# 06_MCU.net
KiCad netlist of a schematic drawn in Altium Designer
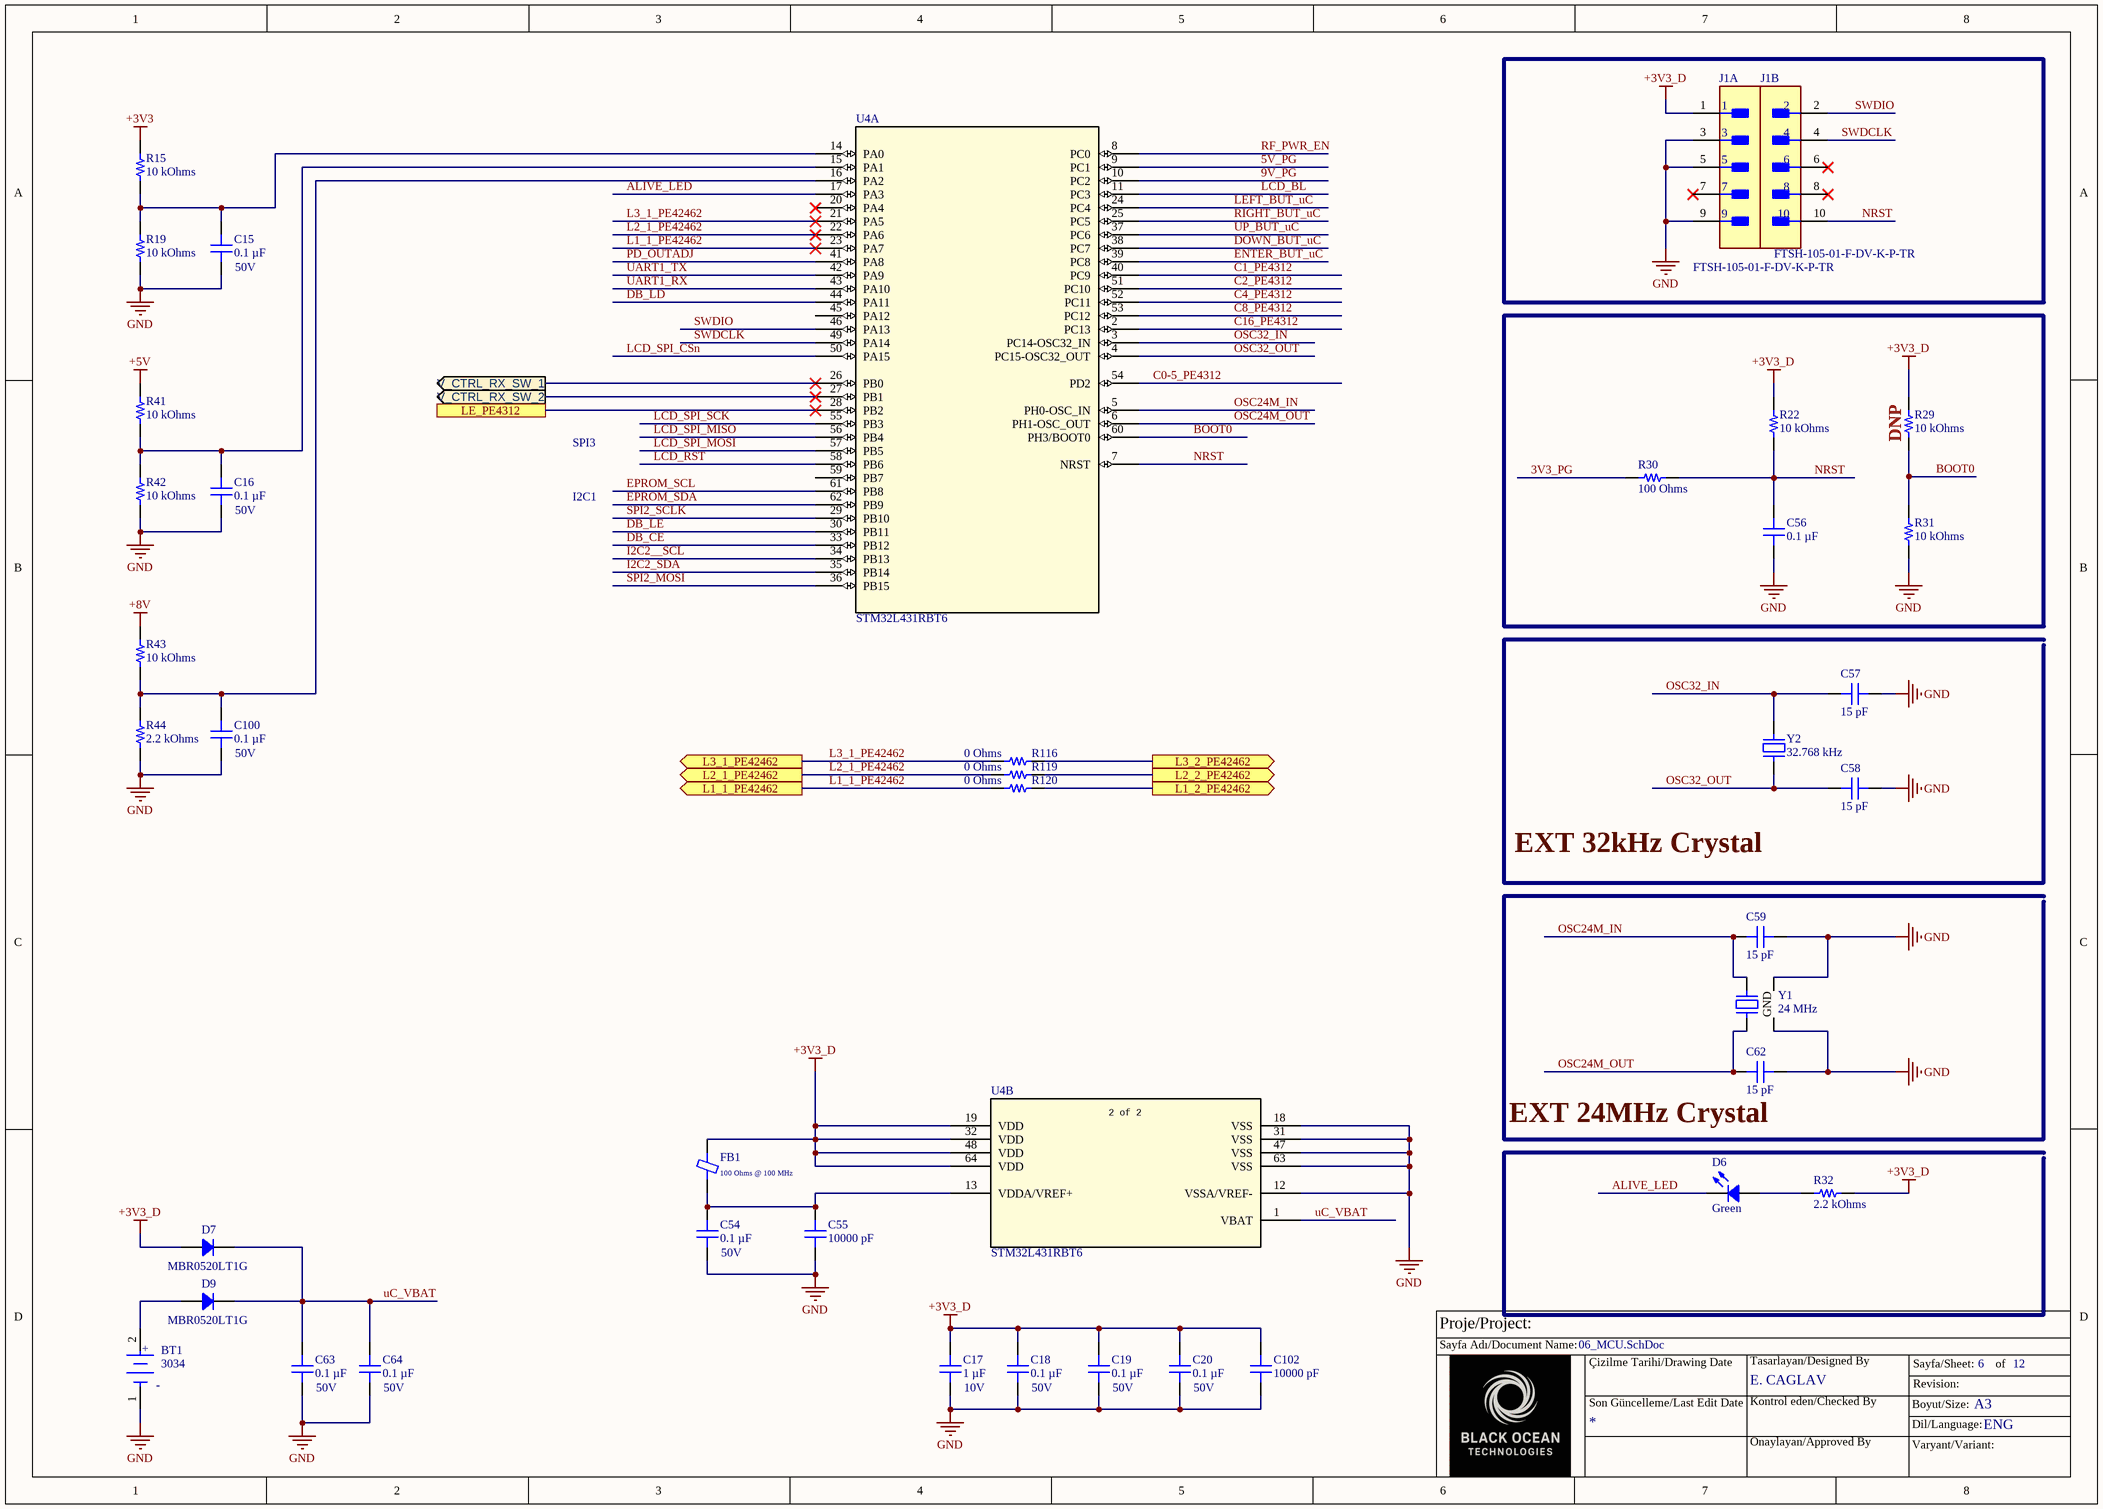
[diagram p0: 06_MCU.SchDoc]

(export (version "E")
  (design (tool "Eeschema 10.0.6"))
  (components
    (comp (ref "BT1")
      (value "3034")
      (footprint "FP-3034-MFG")
      (description "BATTERY RETAINER COIN 20MM SMD")
      (fields
        (field (name "OCTOPART") "https://octopart.com/3034-keystone-27554462")
        (field (name "MANUFACTURER") "Keystone Electronics")
      )
      (libsource (lib "Altium Content Vault") (part "60d3b5b901a8747834971d0eb8cf3fd"))
    )
    (comp (ref "C15")
      (value "0.1 µF")
      (footprint "CAP 0402_1005")
      (description "CAP CER 0.1UF 50V X7R 0402")
      (fields
        (field (name "PART NUMBER") "GCM155R71H104KE02J")
        (field (name "CAPACITANCE") "0.1 µF")
        (field (name "MANUFACTURER") "Murata Electronics")
        (field (name "VOLTAGE - RATED") "50V")
      )
      (libsource (lib "Celestial Altium Library - altium_library") (part "Capacitor"))
    )
    (comp (ref "C16")
      (value "0.1 µF")
      (footprint "CAP 0402_1005")
      (description "CAP CER 0.1UF 50V X7R 0402")
      (fields
        (field (name "PART NUMBER") "GCM155R71H104KE02J")
        (field (name "CAPACITANCE") "0.1 µF")
        (field (name "MANUFACTURER") "Murata Electronics")
        (field (name "VOLTAGE - RATED") "50V")
      )
      (libsource (lib "Celestial Altium Library - altium_library") (part "Capacitor"))
    )
    (comp (ref "C17")
      (value "1 µF")
      (footprint "CAP 0402_1005")
      (description "CAP CER 1UF 10V X7S 0402")
      (fields
        (field (name "PART NUMBER") "GRM155C71A105KE11D")
        (field (name "CAPACITANCE") "1 µF")
        (field (name "MANUFACTURER") "Murata Electronics")
        (field (name "VOLTAGE - RATED") "10V")
      )
      (libsource (lib "Celestial Altium Library - altium_library") (part "Capacitor"))
    )
    (comp (ref "C18")
      (value "0.1 µF")
      (footprint "CAP 0402_1005")
      (description "CAP CER 0.1UF 50V X7R 0402")
      (fields
        (field (name "PART NUMBER") "GCM155R71H104KE02J")
        (field (name "CAPACITANCE") "0.1 µF")
        (field (name "MANUFACTURER") "Murata Electronics")
        (field (name "VOLTAGE - RATED") "50V")
      )
      (libsource (lib "Celestial Altium Library - altium_library") (part "Capacitor"))
    )
    (comp (ref "C19")
      (value "0.1 µF")
      (footprint "CAP 0402_1005")
      (description "CAP CER 0.1UF 50V X7R 0402")
      (fields
        (field (name "PART NUMBER") "GCM155R71H104KE02J")
        (field (name "CAPACITANCE") "0.1 µF")
        (field (name "MANUFACTURER") "Murata Electronics")
        (field (name "VOLTAGE - RATED") "50V")
      )
      (libsource (lib "Celestial Altium Library - altium_library") (part "Capacitor"))
    )
    (comp (ref "C20")
      (value "0.1 µF")
      (footprint "CAP 0402_1005")
      (description "CAP CER 0.1UF 50V X7R 0402")
      (fields
        (field (name "PART NUMBER") "GCM155R71H104KE02J")
        (field (name "CAPACITANCE") "0.1 µF")
        (field (name "MANUFACTURER") "Murata Electronics")
        (field (name "VOLTAGE - RATED") "50V")
      )
      (libsource (lib "Celestial Altium Library - altium_library") (part "Capacitor"))
    )
    (comp (ref "C54")
      (value "0.1 µF")
      (footprint "CAP 0402_1005")
      (description "CAP CER 0.1UF 50V X7R 0402")
      (fields
        (field (name "PART NUMBER") "GCM155R71H104KE02J")
        (field (name "CAPACITANCE") "0.1 µF")
        (field (name "MANUFACTURER") "Murata Electronics")
        (field (name "VOLTAGE - RATED") "50V")
      )
      (libsource (lib "Celestial Altium Library - altium_library") (part "Capacitor"))
    )
    (comp (ref "C55")
      (value "10000 pF")
      (footprint "CAP 0402_1005")
      (description "CAP CER 10000PF 50V X7R 0402")
      (fields
        (field (name "PART NUMBER") "AC0402KPX7R9BB103")
        (field (name "CAPACITANCE") "10000 pF")
        (field (name "MANUFACTURER") "Yageo")
      )
      (libsource (lib "Celestial Altium Library - altium_library") (part "Capacitor"))
    )
    (comp (ref "C56")
      (value "0.1 µF")
      (footprint "CAP 0402_1005")
      (description "CAP CER 0.1UF 50V X7R 0402")
      (fields
        (field (name "PART NUMBER") "GRM155R71H104KE14J")
        (field (name "CAPACITANCE") "0.1 µF")
        (field (name "MANUFACTURER") "Murata Electronics")
      )
      (libsource (lib "Celestial Altium Library - altium_library") (part "Capacitor"))
    )
    (comp (ref "C57")
      (value "15 pF")
      (footprint "CAP 0402_1005")
      (description "CAP CER 15PF 50V C0G/NPO 0402")
      (fields
        (field (name "PART NUMBER") "CC0402GRNPO9BN150")
        (field (name "CAPACITANCE") "15 pF")
        (field (name "MANUFACTURER") "Yageo")
      )
      (libsource (lib "Celestial Altium Library - altium_library") (part "Capacitor"))
    )
    (comp (ref "C58")
      (value "15 pF")
      (footprint "CAP 0402_1005")
      (description "CAP CER 15PF 50V C0G/NPO 0402")
      (fields
        (field (name "PART NUMBER") "CC0402GRNPO9BN150")
        (field (name "CAPACITANCE") "15 pF")
        (field (name "MANUFACTURER") "Yageo")
      )
      (libsource (lib "Celestial Altium Library - altium_library") (part "Capacitor"))
    )
    (comp (ref "C59")
      (value "15 pF")
      (footprint "CAP 0402_1005")
      (description "CAP CER 15PF 50V C0G/NPO 0402")
      (fields
        (field (name "PART NUMBER") "CC0402GRNPO9BN150")
        (field (name "CAPACITANCE") "15 pF")
        (field (name "MANUFACTURER") "Yageo")
      )
      (libsource (lib "Celestial Altium Library - altium_library") (part "Capacitor"))
    )
    (comp (ref "C62")
      (value "15 pF")
      (footprint "CAP 0402_1005")
      (description "CAP CER 15PF 50V C0G/NPO 0402")
      (fields
        (field (name "PART NUMBER") "CC0402GRNPO9BN150")
        (field (name "CAPACITANCE") "15 pF")
        (field (name "MANUFACTURER") "Yageo")
      )
      (libsource (lib "Celestial Altium Library - altium_library") (part "Capacitor"))
    )
    (comp (ref "C63")
      (value "0.1 µF")
      (footprint "CAP 0402_1005")
      (description "CAP CER 0.1UF 50V X7R 0402")
      (fields
        (field (name "PART NUMBER") "GCM155R71H104KE02J")
        (field (name "CAPACITANCE") "0.1 µF")
        (field (name "MANUFACTURER") "Murata Electronics")
        (field (name "VOLTAGE - RATED") "50V")
      )
      (libsource (lib "Celestial Altium Library - altium_library") (part "Capacitor"))
    )
    (comp (ref "C64")
      (value "0.1 µF")
      (footprint "CAP 0402_1005")
      (description "CAP CER 0.1UF 50V X7R 0402")
      (fields
        (field (name "PART NUMBER") "GCM155R71H104KE02J")
        (field (name "CAPACITANCE") "0.1 µF")
        (field (name "MANUFACTURER") "Murata Electronics")
        (field (name "VOLTAGE - RATED") "50V")
      )
      (libsource (lib "Celestial Altium Library - altium_library") (part "Capacitor"))
    )
    (comp (ref "C100")
      (value "0.1 µF")
      (footprint "CAP 0402_1005")
      (description "CAP CER 0.1UF 50V X7R 0402")
      (fields
        (field (name "PART NUMBER") "GCM155R71H104KE02J")
        (field (name "CAPACITANCE") "0.1 µF")
        (field (name "MANUFACTURER") "Murata Electronics")
        (field (name "VOLTAGE - RATED") "50V")
      )
      (libsource (lib "Celestial Altium Library - altium_library") (part "Capacitor"))
    )
    (comp (ref "C102")
      (value "10000 pF")
      (footprint "CAP 0402_1005")
      (description "CAP CER 10000PF 50V X7R 0402")
      (fields
        (field (name "PART NUMBER") "AC0402KPX7R9BB103")
        (field (name "CAPACITANCE") "10000 pF")
        (field (name "MANUFACTURER") "Yageo")
      )
      (libsource (lib "Celestial Altium Library - altium_library") (part "Capacitor"))
    )
    (comp (ref "D6")
      (value "Green")
      (footprint "LED 0603_1608 GREEN")
      (description "LED GREEN 0603 SMD")
      (fields
        (field (name "PART NUMBER") "TLMP1100-GS08")
        (field (name "MANUFACTURER") "Vishay Semiconductor Opto Division")
      )
      (libsource (lib "Celestial Altium Library - altium_library") (part "LED"))
    )
    (comp (ref "D7")
      (value "MBR0520LT1G")
      (footprint "SOD-123")
      (description "DIODE SCHOTTKY 20V 500MA SOD123")
      (fields (field (name "MANUFACTURER") "ON Semiconductor"))
      (libsource (lib "Celestial Altium Library - altium_library") (part "Diode"))
    )
    (comp (ref "D9")
      (value "MBR0520LT1G")
      (footprint "SOD-123")
      (description "DIODE SCHOTTKY 20V 500MA SOD123")
      (fields (field (name "MANUFACTURER") "ON Semiconductor"))
      (libsource (lib "Celestial Altium Library - altium_library") (part "Diode"))
    )
    (comp (ref "FB1")
      (value "100 Ohms @ 100 MHz")
      (footprint "FER 0603_1608")
      (description "FERRITE BEAD 100 OHM 0603 1LN")
      (fields (field (name "PART NUMBER") "MH1608-101Y") (field (name "MANUFACTURER") "Bourns Inc."))
      (libsource (lib "Celestial Altium Library - altium_library") (part "Ferrite Chip"))
    )
    (comp (ref "J1")
      (value "FTSH-105-01-F-DV-K-P-TR")
      (footprint "FP-FTSH-105-01-F-DV-K-P-T-MFG")
      (description "CONN HEADER SMD 10POS 1.27MM")
      (libsource (lib "") (part "544f42128f4185dcb88ce1ce9bf1982_1"))
    )
    (comp (ref "R15")
      (value "10 kOhms")
      (footprint "RES 0402_1005")
      (description "RES 10K OHM 1% 1/16W 0402")
      (fields (field (name "PART NUMBER") "RC0402FR-0710KL") (field (name "MANUFACTURER") "Yageo"))
      (libsource (lib "Celestial Altium Library - altium_library") (part "Resistor"))
    )
    (comp (ref "R19")
      (value "10 kOhms")
      (footprint "RES 0402_1005")
      (description "RES 10K OHM 1% 1/16W 0402")
      (fields (field (name "PART NUMBER") "RC0402FR-0710KL") (field (name "MANUFACTURER") "Yageo"))
      (libsource (lib "Celestial Altium Library - altium_library") (part "Resistor"))
    )
    (comp (ref "R22")
      (value "10 kOhms")
      (footprint "RES 0402_1005")
      (description "RES 10K OHM 1% 1/16W 0402")
      (fields (field (name "PART NUMBER") "RC0402FR-0710KL") (field (name "MANUFACTURER") "Yageo"))
      (libsource (lib "Celestial Altium Library - altium_library") (part "Resistor"))
    )
    (comp (ref "R29")
      (value "10 kOhms")
      (footprint "RES 0402_1005")
      (description "RES 10K OHM 1% 1/16W 0402")
      (fields (field (name "PART NUMBER") "RC0402FR-0710KL") (field (name "MANUFACTURER") "Yageo"))
      (libsource (lib "Celestial Altium Library - altium_library") (part "Resistor"))
    )
    (comp (ref "R30")
      (value "100 Ohms")
      (footprint "RES 0402_1005")
      (description "RES SMD 100 OHM 1% 1/16W 0402")
      (fields (field (name "PART NUMBER") "RT0402FRE07100RL") (field (name "MANUFACTURER") "Yageo"))
      (libsource (lib "Celestial Altium Library - altium_library") (part "Resistor"))
    )
    (comp (ref "R31")
      (value "10 kOhms")
      (footprint "RES 0402_1005")
      (description "RES 10K OHM 1% 1/16W 0402")
      (fields (field (name "PART NUMBER") "RC0402FR-0710KL") (field (name "MANUFACTURER") "Yageo"))
      (libsource (lib "Celestial Altium Library - altium_library") (part "Resistor"))
    )
    (comp (ref "R32")
      (value "2.2 kOhms")
      (footprint "RES 0402_1005")
      (description "RES 2.2K OHM 1% 1/16W 0402")
      (fields
        (field (name "PART NUMBER") "RMCF0402FT2K20")
        (field (name "MANUFACTURER") "Stackpole Electronics Inc")
      )
      (libsource (lib "Celestial Altium Library - altium_library") (part "Resistor"))
    )
    (comp (ref "R41")
      (value "10 kOhms")
      (footprint "RES 0402_1005")
      (description "RES 10K OHM 1% 1/16W 0402")
      (fields (field (name "PART NUMBER") "RC0402FR-0710KL") (field (name "MANUFACTURER") "Yageo"))
      (libsource (lib "Celestial Altium Library - altium_library") (part "Resistor"))
    )
    (comp (ref "R42")
      (value "10 kOhms")
      (footprint "RES 0402_1005")
      (description "RES 10K OHM 1% 1/16W 0402")
      (fields (field (name "PART NUMBER") "RC0402FR-0710KL") (field (name "MANUFACTURER") "Yageo"))
      (libsource (lib "Celestial Altium Library - altium_library") (part "Resistor"))
    )
    (comp (ref "R43")
      (value "10 kOhms")
      (footprint "RES 0402_1005")
      (description "RES 10K OHM 1% 1/16W 0402")
      (fields (field (name "PART NUMBER") "RC0402FR-0710KL") (field (name "MANUFACTURER") "Yageo"))
      (libsource (lib "Celestial Altium Library - altium_library") (part "Resistor"))
    )
    (comp (ref "R44")
      (value "2.2 kOhms")
      (footprint "RES 0402_1005")
      (description "RES 2.2K OHM 1% 1/16W 0402")
      (fields
        (field (name "PART NUMBER") "RMCF0402FT2K20")
        (field (name "MANUFACTURER") "Stackpole Electronics Inc")
      )
      (libsource (lib "Celestial Altium Library - altium_library") (part "Resistor"))
    )
    (comp (ref "R116")
      (value "0 Ohms")
      (footprint "RES 0402_1005")
      (description "RES SMD 0 OHM JUMPER 1/16W 0402")
      (fields (field (name "PART NUMBER") "AC0402JR-070RL") (field (name "MANUFACTURER") "Yageo"))
      (libsource (lib "Celestial Altium Library - altium_library") (part "Resistor"))
    )
    (comp (ref "R119")
      (value "0 Ohms")
      (footprint "RES 0402_1005")
      (description "RES SMD 0 OHM JUMPER 1/16W 0402")
      (fields (field (name "PART NUMBER") "AC0402JR-070RL") (field (name "MANUFACTURER") "Yageo"))
      (libsource (lib "Celestial Altium Library - altium_library") (part "Resistor"))
    )
    (comp (ref "R120")
      (value "0 Ohms")
      (footprint "RES 0402_1005")
      (description "RES SMD 0 OHM JUMPER 1/16W 0402")
      (fields (field (name "PART NUMBER") "AC0402JR-070RL") (field (name "MANUFACTURER") "Yageo"))
      (libsource (lib "Celestial Altium Library - altium_library") (part "Resistor"))
    )
    (comp (ref "U4")
      (value "STM32L431RBT6")
      (footprint "LQFP-64")
      (description "Ultra-low-power with FPU Arm Cortex-M4 MCU 80 MHz with 128 Kbytes of Flash memory")
      (fields (field (name "COPYRIGHT") "Copyright (C) 2026 Ultra Librarian. All rights reserved."))
      (libsource (lib "STM32L431RBT6") (part "STM32L431RBT6"))
    )
    (comp (ref "Y1")
      (value "24 MHz")
      (footprint "EPSON TSX-3225")
      (description "CRYSTAL 24.0000MHZ 9PF SMD")
      (fields (field (name "PART NUMBER") "TSX-3225 24.0000MF20G-AC3") (field (name "MANUFACTURER") "EPSON"))
      (libsource (lib "Celestial Altium Library - altium_library") (part "Epson Crystal TSX-3225"))
    )
    (comp (ref "Y2")
      (value "32.768 kHz")
      (footprint "ABRACON ABS06")
      (description "CRYSTAL 32.7680KHZ 9PF SMD")
      (fields (field (name "PART NUMBER") "ABS06-32.768KHZ-9-T") (field (name "MANUFACTURER") "Abracon LLC"))
      (libsource (lib "Celestial Altium Library - altium_library") (part "Abracon Crystal ABS06"))
    )
  )
  (nets
    (net (code "1") (name "+3V3") (class "Default")
      (node (ref "R15") (pin "2") (pinfunction "2_2") (pintype "passive"))
    )
    (net (code "2") (name "+3V3_D") (class "Default")
      (node (ref "C102") (pin "2") (pinfunction "2_2") (pintype "passive"))
      (node (ref "C17") (pin "1") (pinfunction "1_1") (pintype "passive"))
      (node (ref "C18") (pin "2") (pinfunction "2_2") (pintype "passive"))
      (node (ref "C19") (pin "2") (pinfunction "2_2") (pintype "passive"))
      (node (ref "C20") (pin "2") (pinfunction "2_2") (pintype "passive"))
      (node (ref "D7") (pin "1") (pinfunction "1_1") (pintype "passive"))
      (node (ref "FB1") (pin "2") (pinfunction "2_2") (pintype "passive"))
      (node (ref "J1") (pin "1") (pinfunction "1_1") (pintype "passive"))
      (node (ref "R22") (pin "1") (pinfunction "1_1") (pintype "passive"))
      (node (ref "R29") (pin "1") (pinfunction "1_1") (pintype "passive"))
      (node (ref "R32") (pin "2") (pinfunction "2_2") (pintype "passive"))
      (node (ref "U4") (pin "19") (pinfunction "VDD_19") (pintype "power_in"))
      (node (ref "U4") (pin "32") (pinfunction "VDD_32") (pintype "power_in"))
      (node (ref "U4") (pin "48") (pinfunction "VDD_48") (pintype "power_in"))
      (node (ref "U4") (pin "64") (pinfunction "VDD_64") (pintype "power_in"))
    )
    (net (code "3") (name "+5V") (class "Default")
      (node (ref "R41") (pin "2") (pinfunction "2_2") (pintype "passive"))
    )
    (net (code "4") (name "+8V") (class "Default")
      (node (ref "R43") (pin "2") (pinfunction "2_2") (pintype "passive"))
    )
    (net (code "5") (name "/3V3_PG") (class "Default")
      (node (ref "R30") (pin "1") (pinfunction "1_1") (pintype "passive"))
    )
    (net (code "6") (name "/5V_PG") (class "Default")
      (node (ref "U4") (pin "9") (pinfunction "PC1_9") (pintype "bidirectional"))
    )
    (net (code "7") (name "/9V_PG") (class "Default")
      (node (ref "U4") (pin "10") (pinfunction "PC2_10") (pintype "bidirectional"))
    )
    (net (code "8") (name "/ALIVE_LED") (class "Default")
      (node (ref "D6") (pin "2") (pinfunction "2_2") (pintype "passive"))
      (node (ref "U4") (pin "17") (pinfunction "PA3_17") (pintype "bidirectional"))
    )
    (net (code "9") (name "/BOOT0") (class "Default")
      (node (ref "R29") (pin "2") (pinfunction "2_2") (pintype "passive"))
      (node (ref "R31") (pin "1") (pinfunction "1_1") (pintype "passive"))
      (node (ref "U4") (pin "60") (pinfunction "PH3/BOOT0_60") (pintype "bidirectional"))
    )
    (net (code "10") (name "/C0-5_PE4312") (class "Default")
      (node (ref "U4") (pin "54") (pinfunction "PD2_54") (pintype "bidirectional"))
    )
    (net (code "11") (name "/C1_PE4312") (class "Default")
      (node (ref "U4") (pin "40") (pinfunction "PC9_40") (pintype "bidirectional"))
    )
    (net (code "12") (name "/C2_PE4312") (class "Default")
      (node (ref "U4") (pin "51") (pinfunction "PC10_51") (pintype "bidirectional"))
    )
    (net (code "13") (name "/C4_PE4312") (class "Default")
      (node (ref "U4") (pin "52") (pinfunction "PC11_52") (pintype "bidirectional"))
    )
    (net (code "14") (name "/C8_PE4312") (class "Default")
      (node (ref "U4") (pin "53") (pinfunction "PC12_53") (pintype "bidirectional"))
    )
    (net (code "15") (name "/C16_PE4312") (class "Default")
      (node (ref "U4") (pin "2") (pinfunction "PC13_2") (pintype "bidirectional"))
    )
    (net (code "16") (name "/DB_CE") (class "Default")
      (node (ref "U4") (pin "33") (pinfunction "PB12_33") (pintype "bidirectional"))
    )
    (net (code "17") (name "/DB_LD") (class "Default")
      (node (ref "U4") (pin "44") (pinfunction "PA11_44") (pintype "bidirectional"))
    )
    (net (code "18") (name "/DB_LE") (class "Default")
      (node (ref "U4") (pin "30") (pinfunction "PB11_30") (pintype "bidirectional"))
    )
    (net (code "19") (name "/DOWN_BUT_uC") (class "Default")
      (node (ref "U4") (pin "38") (pinfunction "PC7_38") (pintype "bidirectional"))
    )
    (net (code "20") (name "/ENTER_BUT_uC") (class "Default")
      (node (ref "U4") (pin "39") (pinfunction "PC8_39") (pintype "bidirectional"))
    )
    (net (code "21") (name "/EPROM_SCL") (class "Default")
      (node (ref "U4") (pin "61") (pinfunction "PB8_61") (pintype "bidirectional"))
    )
    (net (code "22") (name "/EPROM_SDA") (class "Default")
      (node (ref "U4") (pin "62") (pinfunction "PB9_62") (pintype "bidirectional"))
    )
    (net (code "23") (name "/I2C2_SDA") (class "Default")
      (node (ref "U4") (pin "35") (pinfunction "PB14_35") (pintype "bidirectional"))
    )
    (net (code "24") (name "/I2C2__SCL") (class "Default")
      (node (ref "U4") (pin "34") (pinfunction "PB13_34") (pintype "bidirectional"))
    )
    (net (code "25") (name "/L1_1_PE42462") (class "Default")
      (node (ref "R120") (pin "1") (pinfunction "1_1") (pintype "passive"))
      (node (ref "U4") (pin "23") (pinfunction "PA7_23") (pintype "bidirectional"))
    )
    (net (code "26") (name "/L1_2_PE42462") (class "Default")
      (node (ref "R120") (pin "2") (pinfunction "2_2") (pintype "passive"))
    )
    (net (code "27") (name "/L2_1_PE42462") (class "Default")
      (node (ref "R119") (pin "1") (pinfunction "1_1") (pintype "passive"))
      (node (ref "U4") (pin "22") (pinfunction "PA6_22") (pintype "bidirectional"))
    )
    (net (code "28") (name "/L2_2_PE42462") (class "Default")
      (node (ref "R119") (pin "2") (pinfunction "2_2") (pintype "passive"))
    )
    (net (code "29") (name "/L3_1_PE42462") (class "Default")
      (node (ref "R116") (pin "1") (pinfunction "1_1") (pintype "passive"))
      (node (ref "U4") (pin "21") (pinfunction "PA5_21") (pintype "bidirectional"))
    )
    (net (code "30") (name "/L3_2_PE42462") (class "Default")
      (node (ref "R116") (pin "2") (pinfunction "2_2") (pintype "passive"))
    )
    (net (code "31") (name "/LCD_BL") (class "Default")
      (node (ref "U4") (pin "11") (pinfunction "PC3_11") (pintype "bidirectional"))
    )
    (net (code "32") (name "/LCD_RST") (class "Default")
      (node (ref "U4") (pin "58") (pinfunction "PB6_58") (pintype "bidirectional"))
    )
    (net (code "33") (name "/LCD_SPI_CSn") (class "Default")
      (node (ref "U4") (pin "50") (pinfunction "PA15_50") (pintype "bidirectional"))
    )
    (net (code "34") (name "/LCD_SPI_MISO") (class "Default")
      (node (ref "U4") (pin "56") (pinfunction "PB4_56") (pintype "bidirectional"))
    )
    (net (code "35") (name "/LCD_SPI_MOSI") (class "Default")
      (node (ref "U4") (pin "57") (pinfunction "PB5_57") (pintype "bidirectional"))
    )
    (net (code "36") (name "/LCD_SPI_SCK") (class "Default")
      (node (ref "U4") (pin "55") (pinfunction "PB3_55") (pintype "bidirectional"))
    )
    (net (code "37") (name "/LEFT_BUT_uC") (class "Default")
      (node (ref "U4") (pin "24") (pinfunction "PC4_24") (pintype "bidirectional"))
    )
    (net (code "38") (name "/LE_PE4312") (class "Default")
      (node (ref "U4") (pin "28") (pinfunction "PB2_28") (pintype "bidirectional+no_connect"))
    )
    (net (code "39") (name "/NRST") (class "Default")
      (node (ref "C56") (pin "2") (pinfunction "2_2") (pintype "passive"))
      (node (ref "J1") (pin "10") (pinfunction "10_10") (pintype "passive"))
      (node (ref "R22") (pin "2") (pinfunction "2_2") (pintype "passive"))
      (node (ref "R30") (pin "2") (pinfunction "2_2") (pintype "passive"))
      (node (ref "U4") (pin "7") (pinfunction "NRST_7") (pintype "bidirectional"))
    )
    (net (code "40") (name "/OSC24M_IN") (class "Default")
      (node (ref "C59") (pin "1") (pinfunction "1_1") (pintype "passive"))
      (node (ref "U4") (pin "5") (pinfunction "PH0-OSC_IN_5") (pintype "bidirectional"))
      (node (ref "Y1") (pin "3") (pinfunction "3_3") (pintype "passive"))
    )
    (net (code "41") (name "/OSC24M_OUT") (class "Default")
      (node (ref "C62") (pin "1") (pinfunction "1_1") (pintype "passive"))
      (node (ref "U4") (pin "6") (pinfunction "PH1-OSC_OUT_6") (pintype "bidirectional"))
      (node (ref "Y1") (pin "1") (pinfunction "1_1") (pintype "passive"))
    )
    (net (code "42") (name "/OSC32_IN") (class "Default")
      (node (ref "C57") (pin "1") (pinfunction "1_1") (pintype "passive"))
      (node (ref "U4") (pin "3") (pinfunction "PC14-OSC32_IN_3") (pintype "bidirectional"))
      (node (ref "Y2") (pin "2") (pinfunction "2_2") (pintype "passive"))
    )
    (net (code "43") (name "/OSC32_OUT") (class "Default")
      (node (ref "C58") (pin "1") (pinfunction "1_1") (pintype "passive"))
      (node (ref "U4") (pin "4") (pinfunction "PC15-OSC32_OUT_4") (pintype "bidirectional"))
      (node (ref "Y2") (pin "1") (pinfunction "1_1") (pintype "passive"))
    )
    (net (code "44") (name "/PD_OUTADJ") (class "Default")
      (node (ref "U4") (pin "41") (pinfunction "PA8_41") (pintype "bidirectional"))
    )
    (net (code "45") (name "/RF_PWR_EN") (class "Default")
      (node (ref "U4") (pin "8") (pinfunction "PC0_8") (pintype "bidirectional"))
    )
    (net (code "46") (name "/RIGHT_BUT_uC") (class "Default")
      (node (ref "U4") (pin "25") (pinfunction "PC5_25") (pintype "bidirectional"))
    )
    (net (code "47") (name "/SPI2_MOSI") (class "Default")
      (node (ref "U4") (pin "36") (pinfunction "PB15_36") (pintype "bidirectional"))
    )
    (net (code "48") (name "/SPI2_SCLK") (class "Default")
      (node (ref "U4") (pin "29") (pinfunction "PB10_29") (pintype "bidirectional"))
    )
    (net (code "49") (name "/SWDCLK") (class "Default")
      (node (ref "J1") (pin "4") (pinfunction "4_4") (pintype "passive"))
      (node (ref "U4") (pin "49") (pinfunction "PA14_49") (pintype "bidirectional"))
    )
    (net (code "50") (name "/SWDIO") (class "Default")
      (node (ref "J1") (pin "2") (pinfunction "2_2") (pintype "passive"))
      (node (ref "U4") (pin "46") (pinfunction "PA13_46") (pintype "bidirectional"))
    )
    (net (code "51") (name "/UART1_RX") (class "Default")
      (node (ref "U4") (pin "43") (pinfunction "PA10_43") (pintype "bidirectional"))
    )
    (net (code "52") (name "/UART1_TX") (class "Default")
      (node (ref "U4") (pin "42") (pinfunction "PA9_42") (pintype "bidirectional"))
    )
    (net (code "53") (name "/UP_BUT_uC") (class "Default")
      (node (ref "U4") (pin "37") (pinfunction "PC6_37") (pintype "bidirectional"))
    )
    (net (code "54") (name "/V_CTRL_RX_SW_1") (class "Default")
      (node (ref "U4") (pin "26") (pinfunction "PB0_26") (pintype "bidirectional+no_connect"))
    )
    (net (code "55") (name "/V_CTRL_RX_SW_2") (class "Default")
      (node (ref "U4") (pin "27") (pinfunction "PB1_27") (pintype "bidirectional+no_connect"))
    )
    (net (code "56") (name "/uC_VBAT") (class "Default")
      (node (ref "C63") (pin "2") (pinfunction "2_2") (pintype "passive"))
      (node (ref "C64") (pin "2") (pinfunction "2_2") (pintype "passive"))
      (node (ref "D7") (pin "2") (pinfunction "2_2") (pintype "passive"))
      (node (ref "D9") (pin "2") (pinfunction "2_2") (pintype "passive"))
      (node (ref "U4") (pin "1") (pinfunction "VBAT_1") (pintype "power_in"))
    )
    (net (code "57") (name "GND") (class "Default")
      (node (ref "BT1") (pin "1") (pinfunction "C_1") (pintype "passive"))
      (node (ref "C100") (pin "1") (pinfunction "1_1") (pintype "passive"))
      (node (ref "C102") (pin "1") (pinfunction "1_1") (pintype "passive"))
      (node (ref "C15") (pin "1") (pinfunction "1_1") (pintype "passive"))
      (node (ref "C16") (pin "1") (pinfunction "1_1") (pintype "passive"))
      (node (ref "C17") (pin "2") (pinfunction "2_2") (pintype "passive"))
      (node (ref "C18") (pin "1") (pinfunction "1_1") (pintype "passive"))
      (node (ref "C19") (pin "1") (pinfunction "1_1") (pintype "passive"))
      (node (ref "C20") (pin "1") (pinfunction "1_1") (pintype "passive"))
      (node (ref "C54") (pin "1") (pinfunction "1_1") (pintype "passive"))
      (node (ref "C55") (pin "1") (pinfunction "1_1") (pintype "passive"))
      (node (ref "C56") (pin "1") (pinfunction "1_1") (pintype "passive"))
      (node (ref "C57") (pin "2") (pinfunction "2_2") (pintype "passive"))
      (node (ref "C58") (pin "2") (pinfunction "2_2") (pintype "passive"))
      (node (ref "C59") (pin "2") (pinfunction "2_2") (pintype "passive"))
      (node (ref "C62") (pin "2") (pinfunction "2_2") (pintype "passive"))
      (node (ref "C63") (pin "1") (pinfunction "1_1") (pintype "passive"))
      (node (ref "C64") (pin "1") (pinfunction "1_1") (pintype "passive"))
      (node (ref "J1") (pin "3") (pinfunction "3_3") (pintype "passive"))
      (node (ref "J1") (pin "5") (pinfunction "5_5") (pintype "passive"))
      (node (ref "J1") (pin "9") (pinfunction "9_9") (pintype "passive"))
      (node (ref "R19") (pin "1") (pinfunction "1_1") (pintype "passive"))
      (node (ref "R31") (pin "2") (pinfunction "2_2") (pintype "passive"))
      (node (ref "R42") (pin "1") (pinfunction "1_1") (pintype "passive"))
      (node (ref "R44") (pin "1") (pinfunction "1_1") (pintype "passive"))
      (node (ref "U4") (pin "12") (pinfunction "VSSA/VREF-_12") (pintype "power_in"))
      (node (ref "U4") (pin "18") (pinfunction "VSS_18") (pintype "power_in"))
      (node (ref "U4") (pin "31") (pinfunction "VSS_31") (pintype "power_in"))
      (node (ref "U4") (pin "47") (pinfunction "VSS_47") (pintype "power_in"))
      (node (ref "U4") (pin "63") (pinfunction "VSS_63") (pintype "power_in"))
      (node (ref "Y1") (pin "2") (pinfunction "GND_2") (pintype "passive"))
      (node (ref "Y1") (pin "4") (pinfunction "GND_4") (pintype "passive"))
    )
    (net (code "58") (name "Net-(BT1-A)") (class "Default")
      (node (ref "BT1") (pin "2") (pinfunction "A_2") (pintype "passive"))
      (node (ref "D9") (pin "1") (pinfunction "1_1") (pintype "passive"))
    )
    (net (code "59") (name "Net-(D6-Pad1)") (class "Default")
      (node (ref "D6") (pin "1") (pinfunction "1_1") (pintype "passive"))
      (node (ref "R32") (pin "1") (pinfunction "1_1") (pintype "passive"))
    )
    (net (code "60") (name "Net-(U4A-PA0)") (class "Default")
      (node (ref "C15") (pin "2") (pinfunction "2_2") (pintype "passive"))
      (node (ref "R15") (pin "1") (pinfunction "1_1") (pintype "passive"))
      (node (ref "R19") (pin "2") (pinfunction "2_2") (pintype "passive"))
      (node (ref "U4") (pin "14") (pinfunction "PA0_14") (pintype "bidirectional"))
    )
    (net (code "61") (name "Net-(U4A-PA1)") (class "Default")
      (node (ref "C16") (pin "2") (pinfunction "2_2") (pintype "passive"))
      (node (ref "R41") (pin "1") (pinfunction "1_1") (pintype "passive"))
      (node (ref "R42") (pin "2") (pinfunction "2_2") (pintype "passive"))
      (node (ref "U4") (pin "15") (pinfunction "PA1_15") (pintype "bidirectional"))
    )
    (net (code "62") (name "Net-(U4A-PA2)") (class "Default")
      (node (ref "C100") (pin "2") (pinfunction "2_2") (pintype "passive"))
      (node (ref "R43") (pin "1") (pinfunction "1_1") (pintype "passive"))
      (node (ref "R44") (pin "2") (pinfunction "2_2") (pintype "passive"))
      (node (ref "U4") (pin "16") (pinfunction "PA2_16") (pintype "bidirectional"))
    )
    (net (code "63") (name "Net-(U4B-VDDA{slash}VREF+)") (class "Default")
      (node (ref "C54") (pin "2") (pinfunction "2_2") (pintype "passive"))
      (node (ref "C55") (pin "2") (pinfunction "2_2") (pintype "passive"))
      (node (ref "FB1") (pin "1") (pinfunction "1_1") (pintype "passive"))
      (node (ref "U4") (pin "13") (pinfunction "VDDA/VREF+_13") (pintype "power_in"))
    )
    (net (code "64") (name "unconnected-(J1-Pad6)") (class "Default")
      (node (ref "J1") (pin "6") (pinfunction "6_6") (pintype "passive+no_connect"))
    )
    (net (code "65") (name "unconnected-(J1-Pad7)") (class "Default")
      (node (ref "J1") (pin "7") (pinfunction "7_7") (pintype "passive+no_connect"))
    )
    (net (code "66") (name "unconnected-(J1-Pad8)") (class "Default")
      (node (ref "J1") (pin "8") (pinfunction "8_8") (pintype "passive+no_connect"))
    )
    (net (code "67") (name "unconnected-(U4A-PA4-Pad20)") (class "Default")
      (node (ref "U4") (pin "20") (pinfunction "PA4_20") (pintype "bidirectional+no_connect"))
    )
    (net (code "68") (name "unconnected-(U4A-PA12-Pad45)") (class "Default")
      (node (ref "U4") (pin "45") (pinfunction "PA12_45") (pintype "bidirectional"))
    )
    (net (code "69") (name "unconnected-(U4A-PB7-Pad59)") (class "Default")
      (node (ref "U4") (pin "59") (pinfunction "PB7_59") (pintype "bidirectional"))
    )
  )
)
